# commadorable64-touch-v1-43.net
KiCad netlist of a schematic drawn in EAGLE
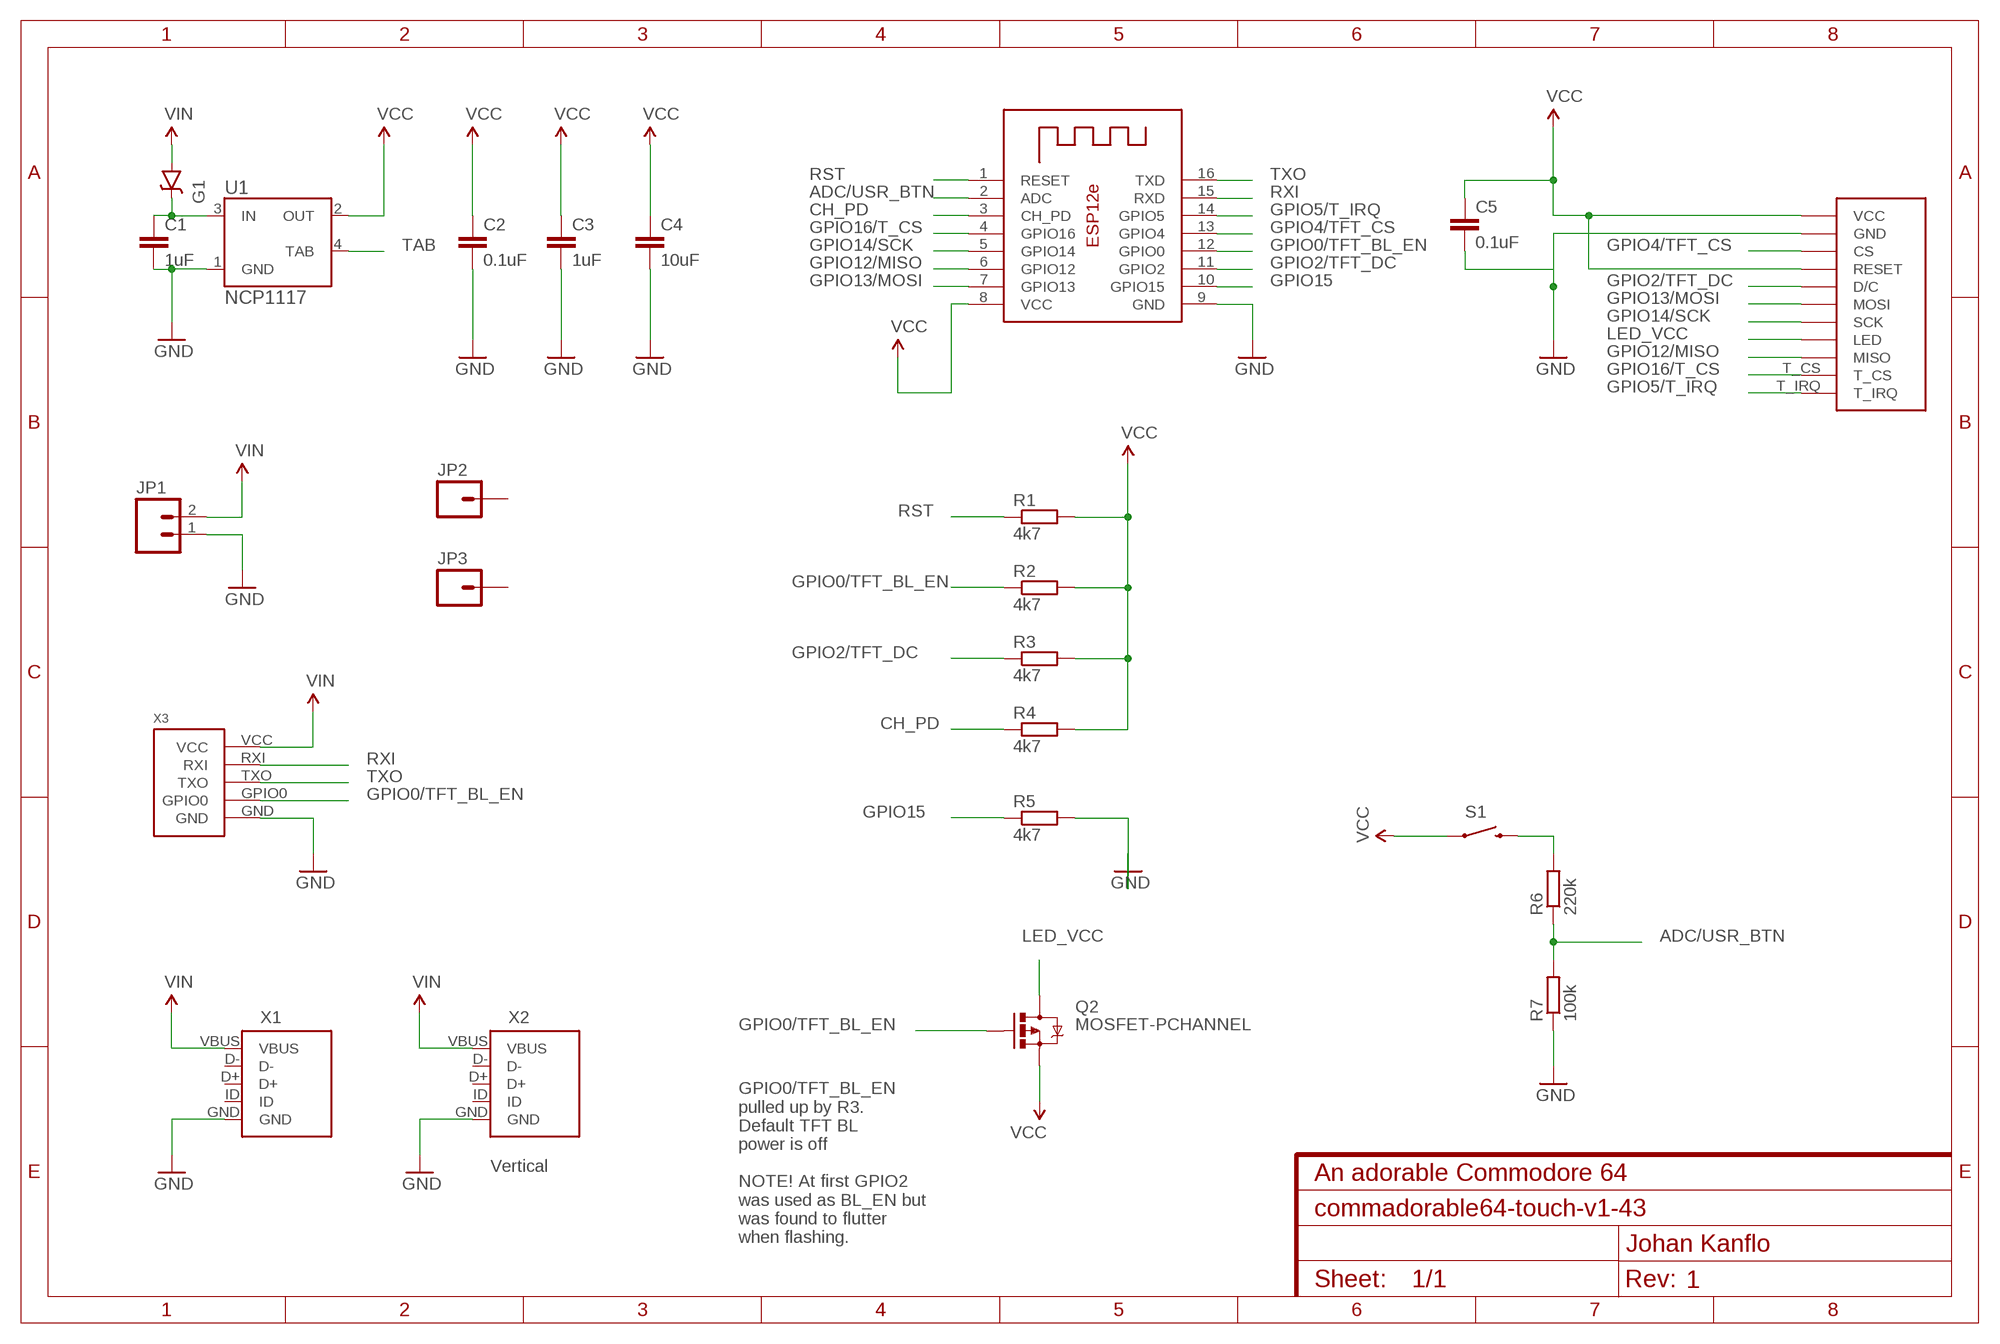
[diagram p0: schematic, sheet 1]

(export (version "E")
  (design (tool "Eeschema 10.0.6"))
  (components
    (comp (ref "C1")
      (value "1uF")
      (footprint "eagle-import:0603-CAP")
      (libsource (lib "eagle-import") (part "CAP0603-CAP"))
    )
    (comp (ref "C2")
      (value "0.1uF")
      (footprint "eagle-import:0603-CAP")
      (libsource (lib "eagle-import") (part "CAP0603-CAP"))
    )
    (comp (ref "C3")
      (value "1uF")
      (footprint "eagle-import:0603-CAP")
      (libsource (lib "eagle-import") (part "CAP0603-CAP"))
    )
    (comp (ref "C4")
      (value "10uF")
      (footprint "eagle-import:0603-CAP")
      (libsource (lib "eagle-import") (part "CAP0603-CAP"))
    )
    (comp (ref "C5")
      (value "0.1uF")
      (footprint "eagle-import:0603-CAP")
      (libsource (lib "eagle-import") (part "CAP0603-CAP"))
    )
    (comp (ref "G1")
      (value "DIODE-SCHOTTKYSOD-123FL")
      (footprint "eagle-import:SOD-123FL")
      (libsource (lib "eagle-import") (part "DIODE-SCHOTTKYSOD-123FL"))
    )
    (comp (ref "J1")
      (value "SPI_TFT_DISPLAY_TOUCH")
      (footprint "eagle-import:SPI_DISPLAY_TOUCH")
      (libsource (lib "eagle-import") (part "SPI_TFT_DISPLAY_TOUCH"))
    )
    (comp (ref "JP1")
      (value "M02PTH")
      (footprint "eagle-import:1X02")
      (libsource (lib "eagle-import") (part "M02PTH"))
    )
    (comp (ref "JP2")
      (value "M01PTH")
      (footprint "eagle-import:1X01")
      (libsource (lib "eagle-import") (part "M01PTH"))
    )
    (comp (ref "JP3")
      (value "M01PTH")
      (footprint "eagle-import:1X01")
      (libsource (lib "eagle-import") (part "M01PTH"))
    )
    (comp (ref "Q2")
      (value "MOSFET-PCHANNEL")
      (footprint "eagle-import:SOT23-3")
      (libsource (lib "eagle-import") (part "MOSFET-PCHANNEL"))
    )
    (comp (ref "R1")
      (value "4k7")
      (footprint "eagle-import:R0603")
      (libsource (lib "eagle-import") (part "R-EU_R0603"))
    )
    (comp (ref "R2")
      (value "4k7")
      (footprint "eagle-import:R0603")
      (libsource (lib "eagle-import") (part "R-EU_R0603"))
    )
    (comp (ref "R3")
      (value "4k7")
      (footprint "eagle-import:R0603")
      (libsource (lib "eagle-import") (part "R-EU_R0603"))
    )
    (comp (ref "R4")
      (value "4k7")
      (footprint "eagle-import:R0603")
      (libsource (lib "eagle-import") (part "R-EU_R0603"))
    )
    (comp (ref "R5")
      (value "4k7")
      (footprint "eagle-import:R0603")
      (libsource (lib "eagle-import") (part "R-EU_R0603"))
    )
    (comp (ref "R6")
      (value "220k")
      (footprint "eagle-import:R0603")
      (libsource (lib "eagle-import") (part "R-EU_R0603"))
    )
    (comp (ref "R7")
      (value "100k")
      (footprint "eagle-import:R0603")
      (libsource (lib "eagle-import") (part "R-EU_R0603"))
    )
    (comp (ref "S1")
      (value "SWITCH-MOMENTARY-2SMD-1101NE")
      (footprint "eagle-import:TACTILE-SWITCH-1101NE")
      (libsource (lib "eagle-import") (part "SWITCH-MOMENTARY-2SMD-1101NE"))
    )
    (comp (ref "U1")
      (value "NCP1117")
      (footprint "eagle-import:SOT223")
      (libsource (lib "eagle-import") (part "NCP1117"))
    )
    (comp (ref "U2")
      (value "ESP-12E")
      (footprint "eagle-import:ESP-12E")
      (libsource (lib "eagle-import") (part "ESP-12E"))
    )
    (comp (ref "X1")
      (value "MICRO_USB_TH")
      (footprint "eagle-import:MICRO_USB_TH")
      (libsource (lib "eagle-import") (part "MICRO_USB_TH"))
    )
    (comp (ref "X2")
      (value "MICRO_USB_TH_VERTICAL")
      (footprint "eagle-import:MICRO_USB_TH_VERTICAL")
      (libsource (lib "eagle-import") (part "MICRO_USB_TH_VERTICAL"))
    )
    (comp (ref "X3")
      (value "ESPROGESPROG-DEVICE")
      (footprint "eagle-import:ESPROG")
      (libsource (lib "eagle-import") (part "ESPROGESPROG-DEVICE"))
    )
  )
  (nets
    (net (code "1") (name "/ADC{slash}USR_BTN") (class "Default")
      (node (ref "R6") (pin "1") (pinfunction "1_1") (pintype "passive"))
      (node (ref "R7") (pin "2") (pinfunction "2_2") (pintype "passive"))
      (node (ref "U2") (pin "2") (pinfunction "ADC_2") (pintype "passive"))
    )
    (net (code "2") (name "/CH_PD") (class "Default")
      (node (ref "R4") (pin "1") (pinfunction "1_1") (pintype "passive"))
      (node (ref "U2") (pin "3") (pinfunction "CH_PD_3") (pintype "input"))
    )
    (net (code "3") (name "/GPIO0{slash}TFT_BL_EN") (class "Default")
      (node (ref "Q2") (pin "1") (pinfunction "G_1") (pintype "passive"))
      (node (ref "R2") (pin "1") (pinfunction "1_1") (pintype "passive"))
      (node (ref "U2") (pin "12") (pinfunction "GPIO0_12") (pintype "bidirectional"))
      (node (ref "X3") (pin "GPIO0") (pinfunction "GPIO0_GPIO0") (pintype "bidirectional"))
    )
    (net (code "4") (name "/GPIO2{slash}TFT_DC") (class "Default")
      (node (ref "J1") (pin "D/C") (pinfunction "D/C_D/C") (pintype "bidirectional"))
      (node (ref "R3") (pin "1") (pinfunction "1_1") (pintype "passive"))
      (node (ref "U2") (pin "11") (pinfunction "GPIO2_11") (pintype "bidirectional"))
    )
    (net (code "5") (name "/GPIO4{slash}TFT_CS") (class "Default")
      (node (ref "J1") (pin "CS") (pinfunction "CS_CS") (pintype "bidirectional"))
      (node (ref "U2") (pin "13") (pinfunction "GPIO4_13") (pintype "bidirectional"))
    )
    (net (code "6") (name "/GPIO5{slash}T_IRQ") (class "Default")
      (node (ref "J1") (pin "T_IRQ") (pinfunction "T_IRQ_T_IRQ") (pintype "bidirectional"))
      (node (ref "U2") (pin "14") (pinfunction "GPIO5_14") (pintype "bidirectional"))
    )
    (net (code "7") (name "/GPIO12{slash}MISO") (class "Default")
      (node (ref "J1") (pin "MISO") (pinfunction "MISO_MISO") (pintype "bidirectional"))
      (node (ref "J1") (pin "T_MISO") (pinfunction "MISO_T_MISO") (pintype "bidirectional"))
      (node (ref "U2") (pin "6") (pinfunction "GPIO12_6") (pintype "bidirectional"))
    )
    (net (code "8") (name "/GPIO13{slash}MOSI") (class "Default")
      (node (ref "J1") (pin "MOSI") (pinfunction "MOSI_MOSI") (pintype "bidirectional"))
      (node (ref "J1") (pin "T_MOSI") (pinfunction "MOSI_T_MOSI") (pintype "bidirectional"))
      (node (ref "U2") (pin "7") (pinfunction "GPIO13_7") (pintype "bidirectional"))
    )
    (net (code "9") (name "/GPIO14{slash}SCK") (class "Default")
      (node (ref "J1") (pin "SCK") (pinfunction "SCK_SCK") (pintype "bidirectional"))
      (node (ref "J1") (pin "T_SCK") (pinfunction "SCK_T_SCK") (pintype "bidirectional"))
      (node (ref "U2") (pin "5") (pinfunction "GPIO14_5") (pintype "bidirectional"))
    )
    (net (code "10") (name "/GPIO15") (class "Default")
      (node (ref "R5") (pin "1") (pinfunction "1_1") (pintype "passive"))
      (node (ref "U2") (pin "10") (pinfunction "GPIO15_10") (pintype "bidirectional"))
    )
    (net (code "11") (name "/GPIO16{slash}T_CS") (class "Default")
      (node (ref "J1") (pin "T_CS") (pinfunction "T_CS_T_CS") (pintype "bidirectional"))
      (node (ref "U2") (pin "4") (pinfunction "GPIO16_4") (pintype "bidirectional"))
    )
    (net (code "12") (name "/LED_VCC") (class "Default")
      (node (ref "J1") (pin "LED") (pinfunction "LED_LED") (pintype "bidirectional"))
      (node (ref "Q2") (pin "3") (pinfunction "D_3") (pintype "passive"))
    )
    (net (code "13") (name "/RST") (class "Default")
      (node (ref "R1") (pin "1") (pinfunction "1_1") (pintype "passive"))
      (node (ref "U2") (pin "1") (pinfunction "RESET_1") (pintype "input"))
    )
    (net (code "14") (name "/RXI") (class "Default")
      (node (ref "U2") (pin "15") (pinfunction "RXD_15") (pintype "input"))
      (node (ref "X3") (pin "RXI") (pinfunction "RXI_RXI") (pintype "bidirectional"))
    )
    (net (code "15") (name "/TAB") (class "Default")
      (node (ref "U1") (pin "4") (pinfunction "TAB_4") (pintype "bidirectional"))
    )
    (net (code "16") (name "/TXO") (class "Default")
      (node (ref "U2") (pin "16") (pinfunction "TXD_16") (pintype "output"))
      (node (ref "X3") (pin "TXO") (pinfunction "TXO_TXO") (pintype "bidirectional"))
    )
    (net (code "17") (name "GND") (class "Default")
      (node (ref "C1") (pin "2") (pinfunction "2_2") (pintype "passive"))
      (node (ref "C2") (pin "2") (pinfunction "2_2") (pintype "passive"))
      (node (ref "C3") (pin "2") (pinfunction "2_2") (pintype "passive"))
      (node (ref "C4") (pin "2") (pinfunction "2_2") (pintype "passive"))
      (node (ref "C5") (pin "2") (pinfunction "2_2") (pintype "passive"))
      (node (ref "J1") (pin "GND") (pinfunction "GND_GND") (pintype "power_in"))
      (node (ref "JP1") (pin "1") (pinfunction "1_1") (pintype "passive"))
      (node (ref "R5") (pin "2") (pinfunction "2_2") (pintype "passive"))
      (node (ref "R7") (pin "1") (pinfunction "1_1") (pintype "passive"))
      (node (ref "U1") (pin "1") (pinfunction "GND_1") (pintype "bidirectional"))
      (node (ref "U2") (pin "9") (pinfunction "GND_9") (pintype "power_in"))
      (node (ref "X1") (pin "GND") (pinfunction "GND_GND") (pintype "power_in"))
      (node (ref "X2") (pin "GND") (pinfunction "GND_GND") (pintype "power_in"))
      (node (ref "X3") (pin "GND") (pinfunction "GND_GND") (pintype "bidirectional"))
    )
    (net (code "18") (name "Net-(R6-Pad2)") (class "Default")
      (node (ref "R6") (pin "2") (pinfunction "2_2") (pintype "passive"))
      (node (ref "S1") (pin "2") (pinfunction "2_2") (pintype "passive"))
    )
    (net (code "19") (name "Net-(U1-IN)") (class "Default")
      (node (ref "C1") (pin "1") (pinfunction "1_1") (pintype "passive"))
      (node (ref "G1") (pin "C") (pinfunction "C_C") (pintype "passive"))
      (node (ref "U1") (pin "3") (pinfunction "IN_3") (pintype "bidirectional"))
    )
    (net (code "20") (name "VCC") (class "Default")
      (node (ref "C2") (pin "1") (pinfunction "1_1") (pintype "passive"))
      (node (ref "C3") (pin "1") (pinfunction "1_1") (pintype "passive"))
      (node (ref "C4") (pin "1") (pinfunction "1_1") (pintype "passive"))
      (node (ref "C5") (pin "1") (pinfunction "1_1") (pintype "passive"))
      (node (ref "J1") (pin "RESET") (pinfunction "RESET_RESET") (pintype "bidirectional"))
      (node (ref "J1") (pin "VCC") (pinfunction "VCC_VCC") (pintype "power_in"))
      (node (ref "Q2") (pin "2") (pinfunction "S_2") (pintype "passive"))
      (node (ref "R1") (pin "2") (pinfunction "2_2") (pintype "passive"))
      (node (ref "R2") (pin "2") (pinfunction "2_2") (pintype "passive"))
      (node (ref "R3") (pin "2") (pinfunction "2_2") (pintype "passive"))
      (node (ref "R4") (pin "2") (pinfunction "2_2") (pintype "passive"))
      (node (ref "S1") (pin "1") (pinfunction "1_1") (pintype "passive"))
      (node (ref "U1") (pin "2") (pinfunction "OUT_2") (pintype "bidirectional"))
      (node (ref "U2") (pin "8") (pinfunction "VCC_8") (pintype "power_in"))
    )
    (net (code "21") (name "VIN") (class "Default")
      (node (ref "G1") (pin "A") (pinfunction "A_A") (pintype "passive"))
      (node (ref "JP1") (pin "2") (pinfunction "2_2") (pintype "passive"))
      (node (ref "X1") (pin "VBUS") (pinfunction "VBUS_VBUS") (pintype "power_in"))
      (node (ref "X2") (pin "VBUS") (pinfunction "VBUS_VBUS") (pintype "power_in"))
      (node (ref "X3") (pin "VCC") (pinfunction "VCC_VCC") (pintype "bidirectional"))
    )
    (net (code "22") (name "unconnected-(JP2-Pad1)") (class "Default")
      (node (ref "JP2") (pin "1") (pinfunction "1_1") (pintype "passive"))
    )
    (net (code "23") (name "unconnected-(JP3-Pad1)") (class "Default")
      (node (ref "JP3") (pin "1") (pinfunction "1_1") (pintype "passive"))
    )
    (net (code "24") (name "unconnected-(X1-PadD+)") (class "Default")
      (node (ref "X1") (pin "D+") (pinfunction "D+_D+") (pintype "bidirectional"))
    )
    (net (code "25") (name "unconnected-(X1-PadD-)") (class "Default")
      (node (ref "X1") (pin "D-") (pinfunction "D-_D-") (pintype "bidirectional"))
    )
    (net (code "26") (name "unconnected-(X1-PadID)") (class "Default")
      (node (ref "X1") (pin "ID") (pinfunction "ID_ID") (pintype "bidirectional"))
    )
    (net (code "27") (name "unconnected-(X2-PadD+)") (class "Default")
      (node (ref "X2") (pin "D+") (pinfunction "D+_D+") (pintype "bidirectional"))
    )
    (net (code "28") (name "unconnected-(X2-PadD-)") (class "Default")
      (node (ref "X2") (pin "D-") (pinfunction "D-_D-") (pintype "bidirectional"))
    )
    (net (code "29") (name "unconnected-(X2-PadID)") (class "Default")
      (node (ref "X2") (pin "ID") (pinfunction "ID_ID") (pintype "bidirectional"))
    )
  )
)
